# untitled.net
KiCad netlist of a schematic drawn in EAGLE
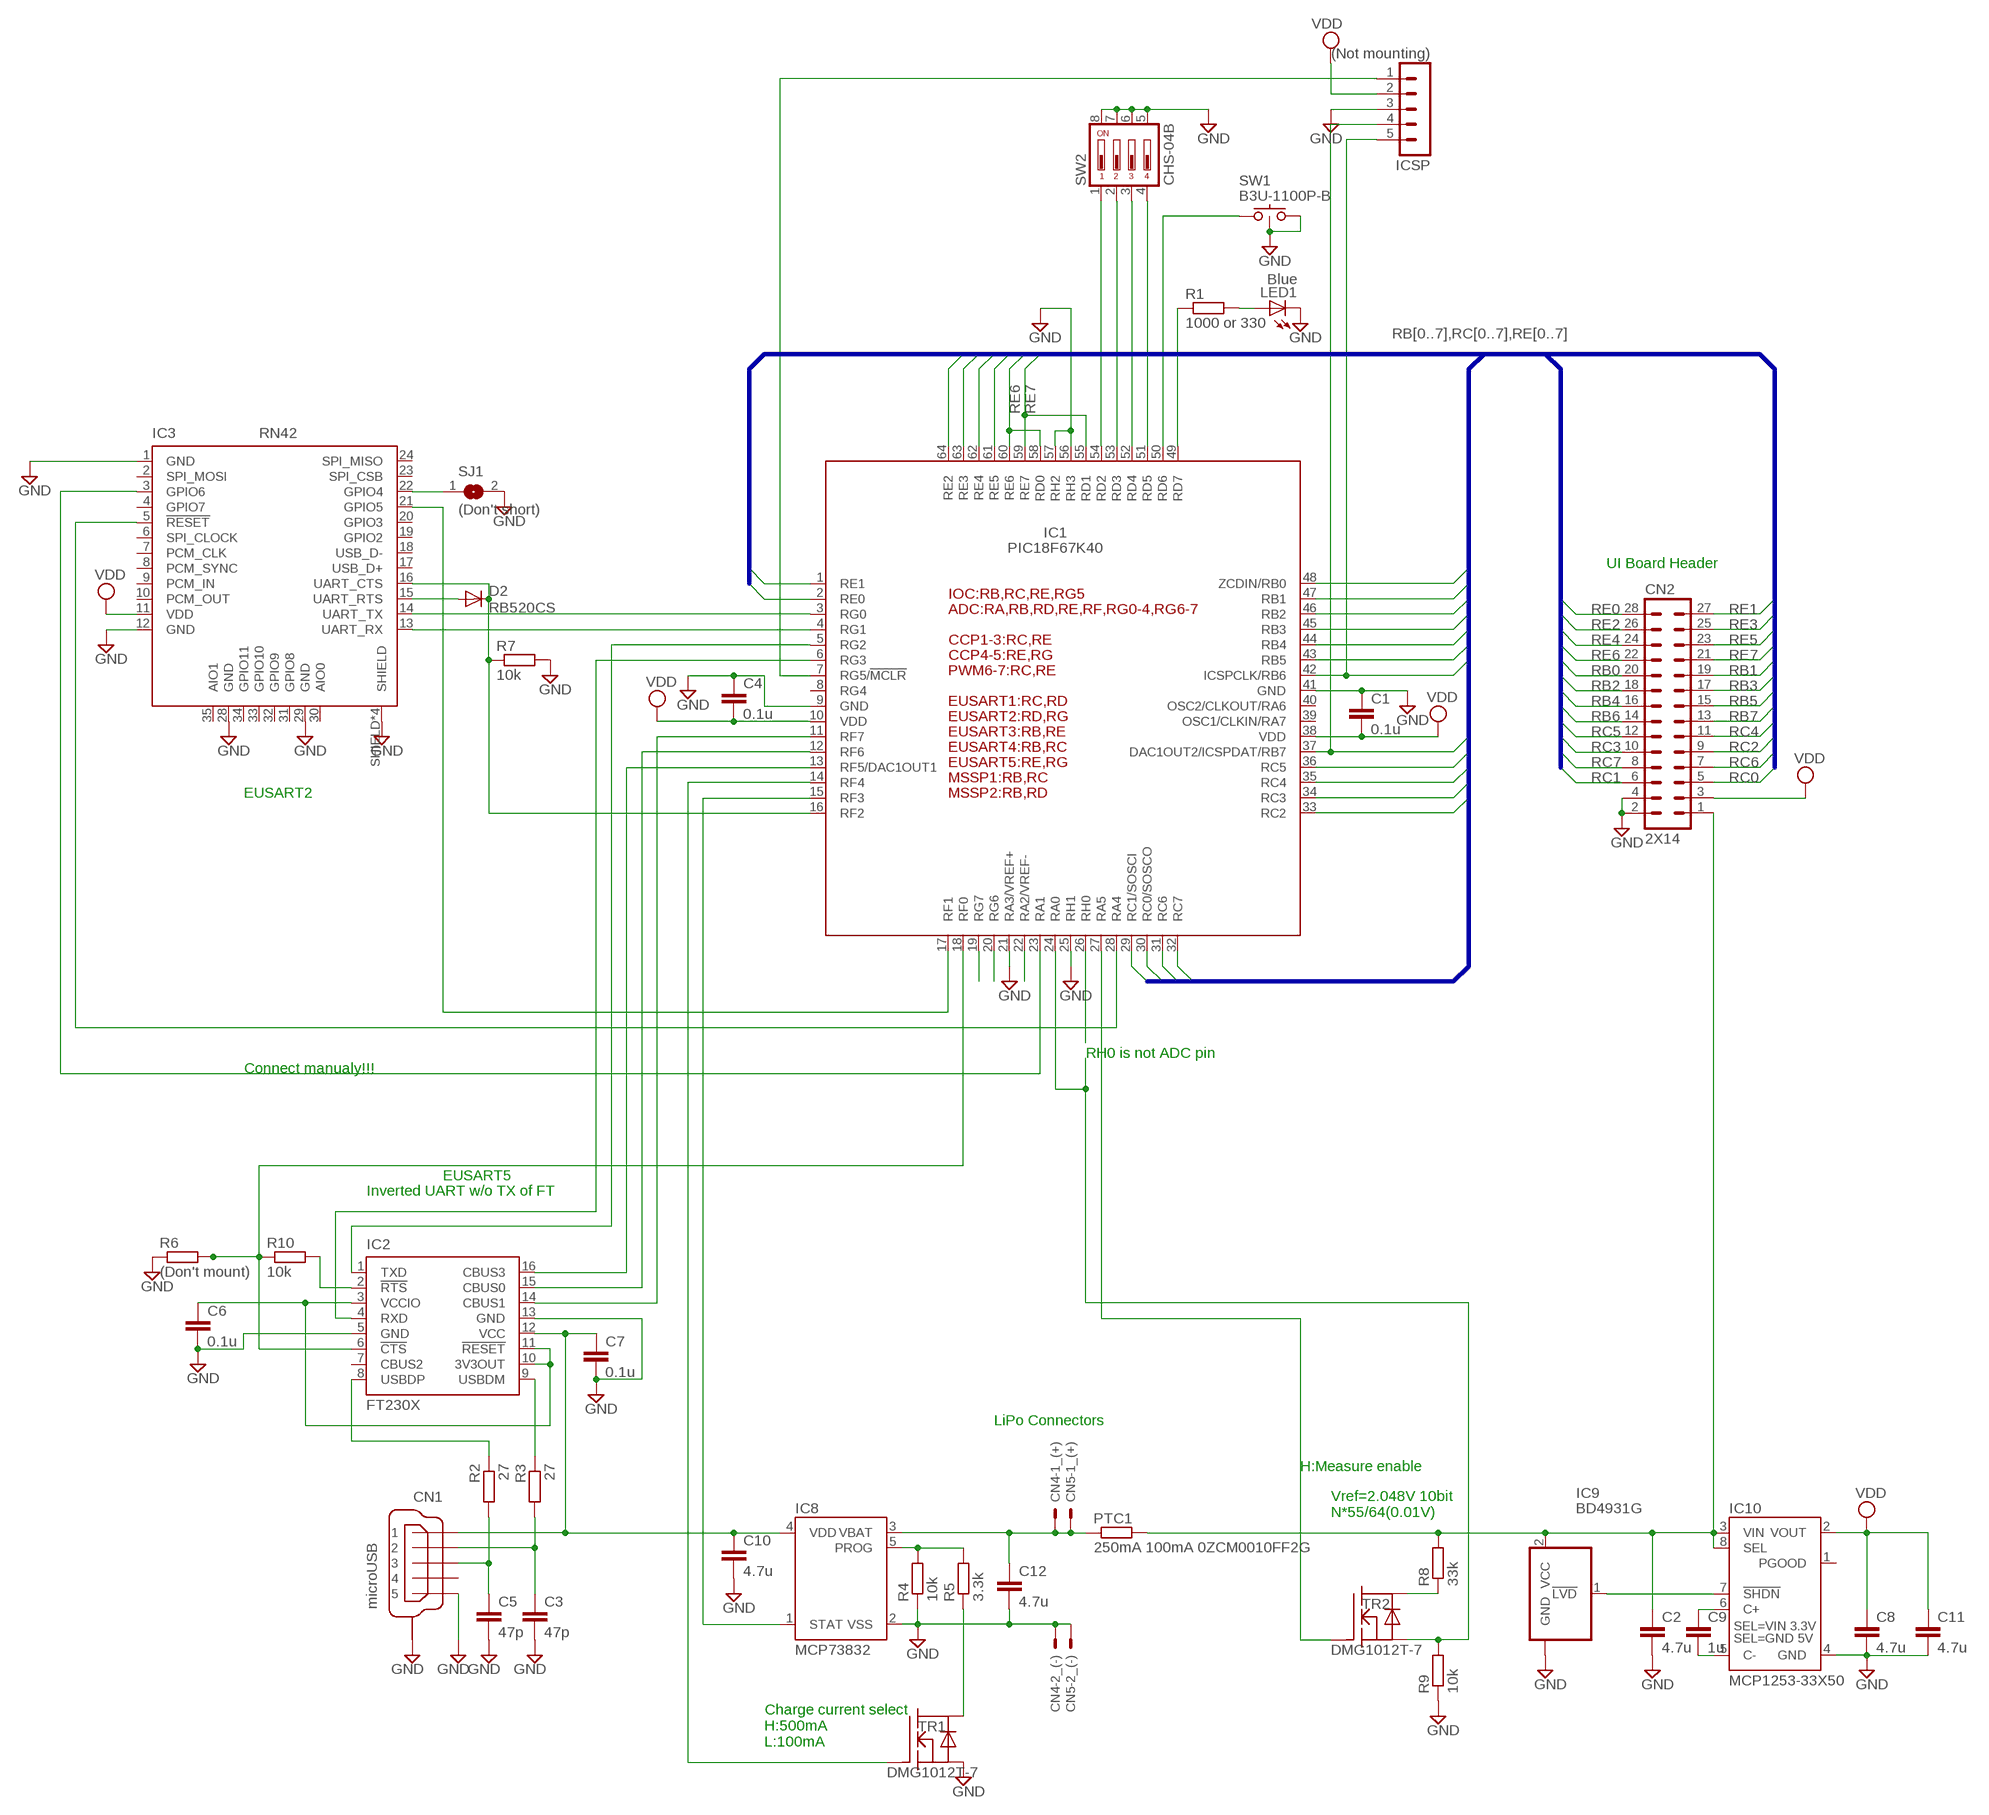
[diagram p0: schematic, sheet 1]

(export (version "E")
  (design (tool "Eeschema 10.0.6"))
  (components
    (comp (ref "C1")
      (value "0.1u")
      (footprint "eagle-import:C0402-SS")
      (libsource (lib "eagle-import") (part "C-EUC0402-SS"))
    )
    (comp (ref "C2")
      (value "4.7u")
      (footprint "eagle-import:C0805")
      (libsource (lib "eagle-import") (part "C-EUC0805"))
    )
    (comp (ref "C3")
      (value "47p")
      (footprint "eagle-import:C0402-SS")
      (libsource (lib "eagle-import") (part "C-EUC0402-SS"))
    )
    (comp (ref "C4")
      (value "0.1u")
      (footprint "eagle-import:C0402-SS")
      (libsource (lib "eagle-import") (part "C-EUC0402-SS"))
    )
    (comp (ref "C5")
      (value "47p")
      (footprint "eagle-import:C0402-SS")
      (libsource (lib "eagle-import") (part "C-EUC0402-SS"))
    )
    (comp (ref "C6")
      (value "0.1u")
      (footprint "eagle-import:C0402-SS")
      (libsource (lib "eagle-import") (part "C-EUC0402-SS"))
    )
    (comp (ref "C7")
      (value "0.1u")
      (footprint "eagle-import:C0402-SS")
      (libsource (lib "eagle-import") (part "C-EUC0402-SS"))
    )
    (comp (ref "C8")
      (value "4.7u")
      (footprint "eagle-import:C0805")
      (libsource (lib "eagle-import") (part "C-EUC0805"))
    )
    (comp (ref "C9")
      (value "1u")
      (footprint "eagle-import:C0805")
      (libsource (lib "eagle-import") (part "C-EUC0805"))
    )
    (comp (ref "C10")
      (value "4.7u")
      (footprint "eagle-import:C0805")
      (libsource (lib "eagle-import") (part "C-EUC0805"))
    )
    (comp (ref "C11")
      (value "4.7u")
      (footprint "eagle-import:C0805")
      (libsource (lib "eagle-import") (part "C-EUC0805"))
    )
    (comp (ref "C12")
      (value "4.7u")
      (footprint "eagle-import:C0805")
      (libsource (lib "eagle-import") (part "C-EUC0805"))
    )
    (comp (ref "CN1")
      (value "microUSB")
      (footprint "eagle-import:10118194-0001LF")
      (libsource (lib "eagle-import") (part "MICROUSB(10118194-0001LF)"))
    )
    (comp (ref "CN2")
      (value "2X14")
      (footprint "eagle-import:2MM_14X2")
      (libsource (lib "eagle-import") (part "2X14"))
    )
    (comp (ref "CN4")
      (value "2P_(POWER)PH_S")
      (footprint "eagle-import:PH-2_S")
      (libsource (lib "eagle-import") (part "2P_(POWER)PH_S"))
    )
    (comp (ref "CN5")
      (value "2P_(POWER)PH_S")
      (footprint "eagle-import:PH-2_S")
      (libsource (lib "eagle-import") (part "2P_(POWER)PH_S"))
    )
    (comp (ref "D2")
      (value "RB520CS")
      (footprint "eagle-import:VMN2")
      (libsource (lib "eagle-import") (part "DIODE-VMN2"))
    )
    (comp (ref "IC1")
      (value "PIC18F67K40")
      (footprint "eagle-import:TQFP64-10X10")
      (libsource (lib "eagle-import") (part "PIC18F67K40"))
    )
    (comp (ref "IC2")
      (value "FT230X")
      (footprint "eagle-import:SSOP16")
      (libsource (lib "eagle-import") (part "FT230XS"))
    )
    (comp (ref "IC3")
      (value "RN42")
      (footprint "eagle-import:RN-42")
      (libsource (lib "eagle-import") (part "RN-42"))
    )
    (comp (ref "IC8")
      (value "MCP73832")
      (footprint "eagle-import:SOT23-5L")
      (libsource (lib "eagle-import") (part "MCP73831"))
    )
    (comp (ref "IC9")
      (value "BD4931G")
      (footprint "eagle-import:SOT23-5L")
      (libsource (lib "eagle-import") (part "BD48XX"))
    )
    (comp (ref "IC10")
      (value "MCP1253-33X50")
      (footprint "eagle-import:MSOP8")
      (libsource (lib "eagle-import") (part "MCP1253-33X50"))
    )
    (comp (ref "ICSP")
      (value "(Not mounting)")
      (footprint "eagle-import:MA05-1")
      (libsource (lib "eagle-import") (part "MA05-1"))
    )
    (comp (ref "LED1")
      (value "Blue")
      (footprint "eagle-import:CHIP-LED1005")
      (libsource (lib "eagle-import") (part "LED1005"))
    )
    (comp (ref "PTC1")
      (value "250mA 100mA 0ZCM0010FF2G")
      (footprint "eagle-import:R0603")
      (libsource (lib "eagle-import") (part "R-EU_R0603"))
    )
    (comp (ref "R1")
      (value "1000 or 330")
      (footprint "eagle-import:R0402-SS")
      (libsource (lib "eagle-import") (part "R-EU_R0402-SS"))
    )
    (comp (ref "R2")
      (value "27")
      (footprint "eagle-import:R0402-SS")
      (libsource (lib "eagle-import") (part "R-EU_R0402-SS"))
    )
    (comp (ref "R3")
      (value "27")
      (footprint "eagle-import:R0402-SS")
      (libsource (lib "eagle-import") (part "R-EU_R0402-SS"))
    )
    (comp (ref "R4")
      (value "10k")
      (footprint "eagle-import:R0402-SS")
      (libsource (lib "eagle-import") (part "R-EU_R0402-SS"))
    )
    (comp (ref "R5")
      (value "3.3k")
      (footprint "eagle-import:R0402-SS")
      (libsource (lib "eagle-import") (part "R-EU_R0402-SS"))
    )
    (comp (ref "R6")
      (value "(Don't mount)")
      (footprint "eagle-import:R0402-SS")
      (libsource (lib "eagle-import") (part "R-EU_R0402-SS"))
    )
    (comp (ref "R7")
      (value "10k")
      (footprint "eagle-import:R0402-SS")
      (libsource (lib "eagle-import") (part "R-EU_R0402-SS"))
    )
    (comp (ref "R8")
      (value "33k")
      (footprint "eagle-import:R0402-SS")
      (libsource (lib "eagle-import") (part "R-EU_R0402-SS"))
    )
    (comp (ref "R9")
      (value "10k")
      (footprint "eagle-import:R0402-SS")
      (libsource (lib "eagle-import") (part "R-EU_R0402-SS"))
    )
    (comp (ref "R10")
      (value "10k")
      (footprint "eagle-import:R0402-SS")
      (libsource (lib "eagle-import") (part "R-EU_R0402-SS"))
    )
    (comp (ref "SJ1")
      (value "(Don't short)")
      (footprint "eagle-import:SJ")
      (libsource (lib "eagle-import") (part "SJ"))
    )
    (comp (ref "SW1")
      (value "B3U-1100P-B")
      (footprint "eagle-import:B3U-1100P-B")
      (libsource (lib "eagle-import") (part "SW_WITH_EARTH(B3U-1100P)"))
    )
    (comp (ref "SW2")
      (value "CHS-04B")
      (footprint "eagle-import:CHS-04B")
      (libsource (lib "eagle-import") (part "CHS-04B"))
    )
    (comp (ref "TR1")
      (value "DMG1012T-7")
      (footprint "eagle-import:SOT523")
      (libsource (lib "eagle-import") (part "NMOSSOT523"))
    )
    (comp (ref "TR2")
      (value "DMG1012T-7")
      (footprint "eagle-import:SOT523")
      (libsource (lib "eagle-import") (part "NMOSSOT523"))
    )
  )
  (nets
    (net (code "1") (name "/RB0") (class "Default")
      (node (ref "CN2") (pin "20") (pinfunction "20_20") (pintype "passive"))
      (node (ref "IC1") (pin "48") (pinfunction "ZCDIN/RB0_48") (pintype "bidirectional"))
    )
    (net (code "2") (name "/RB1") (class "Default")
      (node (ref "CN2") (pin "19") (pinfunction "19_19") (pintype "passive"))
      (node (ref "IC1") (pin "47") (pinfunction "RB1_47") (pintype "bidirectional"))
    )
    (net (code "3") (name "/RB2") (class "Default")
      (node (ref "CN2") (pin "18") (pinfunction "18_18") (pintype "passive"))
      (node (ref "IC1") (pin "46") (pinfunction "RB2_46") (pintype "bidirectional"))
    )
    (net (code "4") (name "/RB3") (class "Default")
      (node (ref "CN2") (pin "17") (pinfunction "17_17") (pintype "passive"))
      (node (ref "IC1") (pin "45") (pinfunction "RB3_45") (pintype "bidirectional"))
    )
    (net (code "5") (name "/RB4") (class "Default")
      (node (ref "CN2") (pin "16") (pinfunction "16_16") (pintype "passive"))
      (node (ref "IC1") (pin "44") (pinfunction "RB4_44") (pintype "bidirectional"))
    )
    (net (code "6") (name "/RB5") (class "Default")
      (node (ref "CN2") (pin "15") (pinfunction "15_15") (pintype "passive"))
      (node (ref "IC1") (pin "43") (pinfunction "RB5_43") (pintype "bidirectional"))
    )
    (net (code "7") (name "/RB6") (class "Default")
      (node (ref "CN2") (pin "14") (pinfunction "14_14") (pintype "passive"))
      (node (ref "IC1") (pin "42") (pinfunction "ICSPCLK/RB6_42") (pintype "bidirectional"))
      (node (ref "ICSP") (pin "5") (pinfunction "5_5") (pintype "passive"))
    )
    (net (code "8") (name "/RB7") (class "Default")
      (node (ref "CN2") (pin "13") (pinfunction "13_13") (pintype "passive"))
      (node (ref "IC1") (pin "37") (pinfunction "DAC1OUT2/ICSPDAT/RB7_37") (pintype "bidirectional"))
      (node (ref "ICSP") (pin "4") (pinfunction "4_4") (pintype "passive"))
    )
    (net (code "9") (name "/RC0") (class "Default")
      (node (ref "CN2") (pin "5") (pinfunction "5_5") (pintype "passive"))
      (node (ref "IC1") (pin "30") (pinfunction "RC0/SOSCO_30") (pintype "bidirectional"))
    )
    (net (code "10") (name "/RC1") (class "Default")
      (node (ref "CN2") (pin "6") (pinfunction "6_6") (pintype "passive"))
      (node (ref "IC1") (pin "29") (pinfunction "RC1/SOSCI_29") (pintype "bidirectional"))
    )
    (net (code "11") (name "/RC2") (class "Default")
      (node (ref "CN2") (pin "9") (pinfunction "9_9") (pintype "passive"))
      (node (ref "IC1") (pin "33") (pinfunction "RC2_33") (pintype "bidirectional"))
    )
    (net (code "12") (name "/RC3") (class "Default")
      (node (ref "CN2") (pin "10") (pinfunction "10_10") (pintype "passive"))
      (node (ref "IC1") (pin "34") (pinfunction "RC3_34") (pintype "bidirectional"))
    )
    (net (code "13") (name "/RC4") (class "Default")
      (node (ref "CN2") (pin "11") (pinfunction "11_11") (pintype "passive"))
      (node (ref "IC1") (pin "35") (pinfunction "RC4_35") (pintype "bidirectional"))
    )
    (net (code "14") (name "/RC5") (class "Default")
      (node (ref "CN2") (pin "12") (pinfunction "12_12") (pintype "passive"))
      (node (ref "IC1") (pin "36") (pinfunction "RC5_36") (pintype "bidirectional"))
    )
    (net (code "15") (name "/RC6") (class "Default")
      (node (ref "CN2") (pin "7") (pinfunction "7_7") (pintype "passive"))
      (node (ref "IC1") (pin "31") (pinfunction "RC6_31") (pintype "bidirectional"))
    )
    (net (code "16") (name "/RC7") (class "Default")
      (node (ref "CN2") (pin "8") (pinfunction "8_8") (pintype "passive"))
      (node (ref "IC1") (pin "32") (pinfunction "RC7_32") (pintype "bidirectional"))
    )
    (net (code "17") (name "/RE0") (class "Default")
      (node (ref "CN2") (pin "28") (pinfunction "28_28") (pintype "passive"))
      (node (ref "IC1") (pin "2") (pinfunction "RE0_2") (pintype "bidirectional"))
    )
    (net (code "18") (name "/RE1") (class "Default")
      (node (ref "CN2") (pin "27") (pinfunction "27_27") (pintype "passive"))
      (node (ref "IC1") (pin "1") (pinfunction "RE1_1") (pintype "bidirectional"))
    )
    (net (code "19") (name "/RE2") (class "Default")
      (node (ref "CN2") (pin "26") (pinfunction "26_26") (pintype "passive"))
      (node (ref "IC1") (pin "64") (pinfunction "RE2_64") (pintype "bidirectional"))
    )
    (net (code "20") (name "/RE3") (class "Default")
      (node (ref "CN2") (pin "25") (pinfunction "25_25") (pintype "passive"))
      (node (ref "IC1") (pin "63") (pinfunction "RE3_63") (pintype "bidirectional"))
    )
    (net (code "21") (name "/RE4") (class "Default")
      (node (ref "CN2") (pin "24") (pinfunction "24_24") (pintype "passive"))
      (node (ref "IC1") (pin "62") (pinfunction "RE4_62") (pintype "bidirectional"))
    )
    (net (code "22") (name "/RE5") (class "Default")
      (node (ref "CN2") (pin "23") (pinfunction "23_23") (pintype "passive"))
      (node (ref "IC1") (pin "61") (pinfunction "RE5_61") (pintype "bidirectional"))
    )
    (net (code "23") (name "/RE6") (class "Default")
      (node (ref "CN2") (pin "22") (pinfunction "22_22") (pintype "passive"))
      (node (ref "IC1") (pin "58") (pinfunction "RD0_58") (pintype "bidirectional"))
      (node (ref "IC1") (pin "60") (pinfunction "RE6_60") (pintype "bidirectional"))
    )
    (net (code "24") (name "/RE7") (class "Default")
      (node (ref "CN2") (pin "21") (pinfunction "21_21") (pintype "passive"))
      (node (ref "IC1") (pin "55") (pinfunction "RD1_55") (pintype "bidirectional"))
      (node (ref "IC1") (pin "59") (pinfunction "RE7_59") (pintype "bidirectional"))
    )
    (net (code "26") (name "GND") (class "Default")
      (node (ref "C1") (pin "1") (pinfunction "1_1") (pintype "passive"))
      (node (ref "C10") (pin "2") (pinfunction "2_2") (pintype "passive"))
      (node (ref "C11") (pin "2") (pinfunction "2_2") (pintype "passive"))
      (node (ref "C12") (pin "2") (pinfunction "2_2") (pintype "passive"))
      (node (ref "C2") (pin "2") (pinfunction "2_2") (pintype "passive"))
      (node (ref "C3") (pin "2") (pinfunction "2_2") (pintype "passive"))
      (node (ref "C4") (pin "1") (pinfunction "1_1") (pintype "passive"))
      (node (ref "C5") (pin "2") (pinfunction "2_2") (pintype "passive"))
      (node (ref "C6") (pin "2") (pinfunction "2_2") (pintype "passive"))
      (node (ref "C7") (pin "2") (pinfunction "2_2") (pintype "passive"))
      (node (ref "C8") (pin "2") (pinfunction "2_2") (pintype "passive"))
      (node (ref "CN1") (pin "P$5") (pinfunction "5_P$5") (pintype "passive"))
      (node (ref "CN1") (pin "P$6") (pinfunction "S_P$6") (pintype "passive"))
      (node (ref "CN1") (pin "P$7") (pinfunction "S_P$7") (pintype "passive"))
      (node (ref "CN1") (pin "S1") (pinfunction "S_S1") (pintype "passive"))
      (node (ref "CN1") (pin "S10") (pinfunction "S_S10") (pintype "passive"))
      (node (ref "CN1") (pin "S2") (pinfunction "S_S2") (pintype "passive"))
      (node (ref "CN1") (pin "S3") (pinfunction "S_S3") (pintype "passive"))
      (node (ref "CN1") (pin "S4") (pinfunction "S_S4") (pintype "passive"))
      (node (ref "CN1") (pin "S5") (pinfunction "S_S5") (pintype "passive"))
      (node (ref "CN1") (pin "S6") (pinfunction "S_S6") (pintype "passive"))
      (node (ref "CN1") (pin "S7") (pinfunction "S_S7") (pintype "passive"))
      (node (ref "CN1") (pin "S8") (pinfunction "S_S8") (pintype "passive"))
      (node (ref "CN1") (pin "S9") (pinfunction "S_S9") (pintype "passive"))
      (node (ref "CN2") (pin "2") (pinfunction "2_2") (pintype "passive"))
      (node (ref "CN2") (pin "4") (pinfunction "4_4") (pintype "passive"))
      (node (ref "CN4") (pin "2") (pinfunction "S_2") (pintype "passive"))
      (node (ref "CN5") (pin "2") (pinfunction "S_2") (pintype "passive"))
      (node (ref "IC1") (pin "21") (pinfunction "RA3/VREF+_21") (pintype "bidirectional"))
      (node (ref "IC1") (pin "25") (pinfunction "RH1_25") (pintype "bidirectional"))
      (node (ref "IC1") (pin "41") (pinfunction "GND_41") (pintype "power_in"))
      (node (ref "IC1") (pin "56") (pinfunction "RH3_56") (pintype "bidirectional"))
      (node (ref "IC1") (pin "57") (pinfunction "RH2_57") (pintype "bidirectional"))
      (node (ref "IC1") (pin "9") (pinfunction "GND_9") (pintype "power_in"))
      (node (ref "IC10") (pin "4") (pinfunction "GND_4") (pintype "power_in"))
      (node (ref "IC2") (pin "13") (pinfunction "GND_13") (pintype "power_in"))
      (node (ref "IC2") (pin "5") (pinfunction "GND_5") (pintype "power_in"))
      (node (ref "IC3") (pin "1") (pinfunction "GND_1") (pintype "bidirectional"))
      (node (ref "IC3") (pin "12") (pinfunction "GND_12") (pintype "bidirectional"))
      (node (ref "IC3") (pin "28") (pinfunction "GND_28") (pintype "bidirectional"))
      (node (ref "IC3") (pin "29") (pinfunction "GND_29") (pintype "bidirectional"))
      (node (ref "IC3") (pin "SHIELD") (pinfunction "SHIELD_SHIELD") (pintype "bidirectional"))
      (node (ref "IC3") (pin "SHIELD@1") (pinfunction "SHIELD_SHIELD@1") (pintype "bidirectional"))
      (node (ref "IC3") (pin "SHIELD@2") (pinfunction "SHIELD_SHIELD@2") (pintype "bidirectional"))
      (node (ref "IC3") (pin "SHIELD@3") (pinfunction "SHIELD_SHIELD@3") (pintype "bidirectional"))
      (node (ref "IC8") (pin "2") (pinfunction "VSS_2") (pintype "power_in"))
      (node (ref "IC9") (pin "3") (pinfunction "GND_3") (pintype "power_in"))
      (node (ref "ICSP") (pin "3") (pinfunction "3_3") (pintype "passive"))
      (node (ref "LED1") (pin "C") (pinfunction "C_C") (pintype "passive"))
      (node (ref "R4") (pin "1") (pinfunction "1_1") (pintype "passive"))
      (node (ref "R6") (pin "1") (pinfunction "1_1") (pintype "passive"))
      (node (ref "R7") (pin "2") (pinfunction "2_2") (pintype "passive"))
      (node (ref "R9") (pin "1") (pinfunction "1_1") (pintype "passive"))
      (node (ref "SJ1") (pin "2") (pinfunction "2_2") (pintype "passive"))
      (node (ref "SW1") (pin "P$2") (pinfunction "P$2_P$2") (pintype "passive"))
      (node (ref "SW1") (pin "P$3") (pinfunction "P$3_P$3") (pintype "passive"))
      (node (ref "SW2") (pin "5") (pinfunction "5_5") (pintype "passive"))
      (node (ref "SW2") (pin "6") (pinfunction "6_6") (pintype "passive"))
      (node (ref "SW2") (pin "7") (pinfunction "7_7") (pintype "passive"))
      (node (ref "SW2") (pin "8") (pinfunction "8_8") (pintype "passive"))
      (node (ref "TR1") (pin "2") (pinfunction "S_2") (pintype "bidirectional"))
    )
    (net (code "27") (name "Net-(CN1-1)") (class "Default")
      (node (ref "C10") (pin "1") (pinfunction "1_1") (pintype "passive"))
      (node (ref "C7") (pin "1") (pinfunction "1_1") (pintype "passive"))
      (node (ref "CN1") (pin "P$1") (pinfunction "1_P$1") (pintype "passive"))
      (node (ref "IC2") (pin "12") (pinfunction "VCC_12") (pintype "power_in"))
      (node (ref "IC8") (pin "4") (pinfunction "VDD_4") (pintype "power_in"))
    )
    (net (code "28") (name "Net-(CN1-2)") (class "Default")
      (node (ref "C3") (pin "1") (pinfunction "1_1") (pintype "passive"))
      (node (ref "CN1") (pin "P$2") (pinfunction "2_P$2") (pintype "passive"))
      (node (ref "R3") (pin "2") (pinfunction "2_2") (pintype "passive"))
    )
    (net (code "29") (name "Net-(CN1-3)") (class "Default")
      (node (ref "C5") (pin "1") (pinfunction "1_1") (pintype "passive"))
      (node (ref "CN1") (pin "P$3") (pinfunction "3_P$3") (pintype "passive"))
      (node (ref "R2") (pin "2") (pinfunction "2_2") (pintype "passive"))
    )
    (net (code "30") (name "Net-(CN4A-S)") (class "Default")
      (node (ref "C12") (pin "1") (pinfunction "1_1") (pintype "passive"))
      (node (ref "CN4") (pin "1") (pinfunction "S_1") (pintype "passive"))
      (node (ref "CN5") (pin "1") (pinfunction "S_1") (pintype "passive"))
      (node (ref "IC8") (pin "3") (pinfunction "VBAT_3") (pintype "output"))
      (node (ref "PTC1") (pin "1") (pinfunction "1_1") (pintype "passive"))
    )
    (net (code "31") (name "Net-(IC1-RA0)") (class "Default")
      (node (ref "IC1") (pin "24") (pinfunction "RA0_24") (pintype "bidirectional"))
      (node (ref "R9") (pin "2") (pinfunction "2_2") (pintype "passive"))
      (node (ref "TR2") (pin "2") (pinfunction "S_2") (pintype "bidirectional"))
    )
    (net (code "32") (name "Net-(IC1-RA1)") (class "Default")
      (node (ref "IC1") (pin "23") (pinfunction "RA1_23") (pintype "bidirectional"))
      (node (ref "IC3") (pin "3") (pinfunction "GPIO6_3") (pintype "bidirectional"))
    )
    (net (code "33") (name "Net-(IC1-RA4)") (class "Default")
      (node (ref "IC1") (pin "28") (pinfunction "RA4_28") (pintype "bidirectional"))
      (node (ref "IC3") (pin "5") (pinfunction "~{RESET}_5") (pintype "bidirectional"))
    )
    (net (code "34") (name "Net-(IC1-RA5)") (class "Default")
      (node (ref "IC1") (pin "27") (pinfunction "RA5_27") (pintype "bidirectional"))
      (node (ref "TR2") (pin "1") (pinfunction "G_1") (pintype "bidirectional"))
    )
    (net (code "35") (name "Net-(IC1-RD2)") (class "Default")
      (node (ref "IC1") (pin "54") (pinfunction "RD2_54") (pintype "bidirectional"))
      (node (ref "SW2") (pin "1") (pinfunction "1_1") (pintype "passive"))
    )
    (net (code "36") (name "Net-(IC1-RD3)") (class "Default")
      (node (ref "IC1") (pin "53") (pinfunction "RD3_53") (pintype "bidirectional"))
      (node (ref "SW2") (pin "2") (pinfunction "2_2") (pintype "passive"))
    )
    (net (code "37") (name "Net-(IC1-RD4)") (class "Default")
      (node (ref "IC1") (pin "52") (pinfunction "RD4_52") (pintype "bidirectional"))
      (node (ref "SW2") (pin "3") (pinfunction "3_3") (pintype "passive"))
    )
    (net (code "38") (name "Net-(IC1-RD5)") (class "Default")
      (node (ref "IC1") (pin "51") (pinfunction "RD5_51") (pintype "bidirectional"))
      (node (ref "SW2") (pin "4") (pinfunction "4_4") (pintype "passive"))
    )
    (net (code "39") (name "Net-(IC1-RD6)") (class "Default")
      (node (ref "IC1") (pin "50") (pinfunction "RD6_50") (pintype "bidirectional"))
      (node (ref "SW1") (pin "P$1") (pinfunction "P$1_P$1") (pintype "passive"))
    )
    (net (code "40") (name "Net-(IC1-RD7)") (class "Default")
      (node (ref "IC1") (pin "49") (pinfunction "RD7_49") (pintype "bidirectional"))
      (node (ref "R1") (pin "1") (pinfunction "1_1") (pintype "passive"))
    )
    (net (code "41") (name "Net-(IC1-RF0)") (class "Default")
      (node (ref "IC1") (pin "18") (pinfunction "RF0_18") (pintype "bidirectional"))
      (node (ref "IC2") (pin "6") (pinfunction "~{CTS}_6") (pintype "input"))
      (node (ref "R10") (pin "1") (pinfunction "1_1") (pintype "passive"))
      (node (ref "R6") (pin "2") (pinfunction "2_2") (pintype "passive"))
    )
    (net (code "42") (name "Net-(IC1-RF1)") (class "Default")
      (node (ref "IC1") (pin "17") (pinfunction "RF1_17") (pintype "bidirectional"))
      (node (ref "IC3") (pin "21") (pinfunction "GPIO5_21") (pintype "bidirectional"))
    )
    (net (code "43") (name "Net-(IC1-RF2)") (class "Default")
      (node (ref "D2") (pin "C") (pinfunction "C_C") (pintype "passive"))
      (node (ref "IC1") (pin "16") (pinfunction "RF2_16") (pintype "bidirectional"))
      (node (ref "IC3") (pin "16") (pinfunction "UART_CTS_16") (pintype "bidirectional"))
      (node (ref "R7") (pin "1") (pinfunction "1_1") (pintype "passive"))
    )
    (net (code "44") (name "Net-(IC1-RF3)") (class "Default")
      (node (ref "IC1") (pin "15") (pinfunction "RF3_15") (pintype "bidirectional"))
      (node (ref "IC8") (pin "1") (pinfunction "STAT_1") (pintype "output"))
    )
    (net (code "45") (name "Net-(IC1-RF4)") (class "Default")
      (node (ref "IC1") (pin "14") (pinfunction "RF4_14") (pintype "bidirectional"))
      (node (ref "TR1") (pin "1") (pinfunction "G_1") (pintype "bidirectional"))
    )
    (net (code "46") (name "Net-(IC1-RF5{slash}DAC1OUT1)") (class "Default")
      (node (ref "IC1") (pin "13") (pinfunction "RF5/DAC1OUT1_13") (pintype "bidirectional"))
      (node (ref "IC2") (pin "16") (pinfunction "CBUS3_16") (pintype "bidirectional"))
    )
    (net (code "47") (name "Net-(IC1-RF6)") (class "Default")
      (node (ref "IC1") (pin "12") (pinfunction "RF6_12") (pintype "bidirectional"))
      (node (ref "IC2") (pin "15") (pinfunction "CBUS0_15") (pintype "bidirectional"))
    )
    (net (code "48") (name "Net-(IC1-RF7)") (class "Default")
      (node (ref "IC1") (pin "11") (pinfunction "RF7_11") (pintype "bidirectional"))
      (node (ref "IC2") (pin "14") (pinfunction "CBUS1_14") (pintype "bidirectional"))
    )
    (net (code "49") (name "Net-(IC1-RG0)") (class "Default")
      (node (ref "IC1") (pin "3") (pinfunction "RG0_3") (pintype "bidirectional"))
      (node (ref "IC3") (pin "14") (pinfunction "UART_TX_14") (pintype "bidirectional"))
    )
    (net (code "50") (name "Net-(IC1-RG1)") (class "Default")
      (node (ref "IC1") (pin "4") (pinfunction "RG1_4") (pintype "bidirectional"))
      (node (ref "IC3") (pin "13") (pinfunction "UART_RX_13") (pintype "bidirectional"))
    )
    (net (code "51") (name "Net-(IC1-RG2)") (class "Default")
      (node (ref "IC1") (pin "5") (pinfunction "RG2_5") (pintype "bidirectional"))
      (node (ref "IC2") (pin "1") (pinfunction "TXD_1") (pintype "output"))
    )
    (net (code "52") (name "Net-(IC1-RG3)") (class "Default")
      (node (ref "IC1") (pin "6") (pinfunction "RG3_6") (pintype "bidirectional"))
      (node (ref "IC2") (pin "4") (pinfunction "RXD_4") (pintype "input"))
    )
    (net (code "53") (name "Net-(IC1-RG5{slash}~{MCLR})") (class "Default")
      (node (ref "IC1") (pin "7") (pinfunction "RG5/~{MCLR}_7") (pintype "input"))
      (node (ref "ICSP") (pin "1") (pinfunction "1_1") (pintype "passive"))
    )
    (net (code "54") (name "Net-(IC2-3V3OUT)") (class "Default")
      (node (ref "C6") (pin "1") (pinfunction "1_1") (pintype "passive"))
      (node (ref "IC2") (pin "10") (pinfunction "3V3OUT_10") (pintype "output"))
      (node (ref "IC2") (pin "11") (pinfunction "~{RESET}_11") (pintype "input"))
      (node (ref "IC2") (pin "3") (pinfunction "VCCIO_3") (pintype "power_in"))
    )
    (net (code "55") (name "Net-(IC2-USBDM)") (class "Default")
      (node (ref "IC2") (pin "9") (pinfunction "USBDM_9") (pintype "input"))
      (node (ref "R3") (pin "1") (pinfunction "1_1") (pintype "passive"))
    )
    (net (code "56") (name "Net-(IC2-USBDP)") (class "Default")
      (node (ref "IC2") (pin "8") (pinfunction "USBDP_8") (pintype "input"))
      (node (ref "R2") (pin "1") (pinfunction "1_1") (pintype "passive"))
    )
    (net (code "57") (name "Net-(IC2-~{RTS})") (class "Default")
      (node (ref "IC2") (pin "2") (pinfunction "~{RTS}_2") (pintype "output"))
      (node (ref "R10") (pin "2") (pinfunction "2_2") (pintype "passive"))
    )
    (net (code "58") (name "Net-(IC3-GPIO4)") (class "Default")
      (node (ref "IC3") (pin "22") (pinfunction "GPIO4_22") (pintype "bidirectional"))
      (node (ref "SJ1") (pin "1") (pinfunction "1_1") (pintype "passive"))
    )
    (net (code "59") (name "Net-(IC3-UART_RTS)") (class "Default")
      (node (ref "D2") (pin "A") (pinfunction "A_A") (pintype "passive"))
      (node (ref "IC3") (pin "15") (pinfunction "UART_RTS_15") (pintype "bidirectional"))
    )
    (net (code "60") (name "Net-(IC8-PROG)") (class "Default")
      (node (ref "IC8") (pin "5") (pinfunction "PROG_5") (pintype "input"))
      (node (ref "R4") (pin "2") (pinfunction "2_2") (pintype "passive"))
      (node (ref "R5") (pin "2") (pinfunction "2_2") (pintype "passive"))
    )
    (net (code "61") (name "Net-(IC10-C+)") (class "Default")
      (node (ref "C9") (pin "1") (pinfunction "1_1") (pintype "passive"))
      (node (ref "IC10") (pin "6") (pinfunction "C+_6") (pintype "passive"))
    )
    (net (code "62") (name "Net-(IC10-C-)") (class "Default")
      (node (ref "C9") (pin "2") (pinfunction "2_2") (pintype "passive"))
      (node (ref "IC10") (pin "5") (pinfunction "C-_5") (pintype "passive"))
    )
    (net (code "63") (name "Net-(IC10-SEL)") (class "Default")
      (node (ref "C2") (pin "1") (pinfunction "1_1") (pintype "passive"))
      (node (ref "CN2") (pin "1") (pinfunction "1_1") (pintype "passive"))
      (node (ref "IC10") (pin "3") (pinfunction "VIN_3") (pintype "power_in"))
      (node (ref "IC10") (pin "8") (pinfunction "SEL_8") (pintype "input"))
      (node (ref "IC9") (pin "2") (pinfunction "VCC_2") (pintype "power_in"))
      (node (ref "PTC1") (pin "2") (pinfunction "2_2") (pintype "passive"))
      (node (ref "R8") (pin "2") (pinfunction "2_2") (pintype "passive"))
    )
    (net (code "64") (name "Net-(IC10-~{SHDN})") (class "Default")
      (node (ref "IC10") (pin "7") (pinfunction "~{SHDN}_7") (pintype "input"))
      (node (ref "IC9") (pin "1") (pinfunction "~{LVD}_1") (pintype "output"))
    )
    (net (code "65") (name "Net-(LED1-PadA)") (class "Default")
      (node (ref "LED1") (pin "A") (pinfunction "A_A") (pintype "passive"))
      (node (ref "R1") (pin "2") (pinfunction "2_2") (pintype "passive"))
    )
    (net (code "66") (name "Net-(TR1-D)") (class "Default")
      (node (ref "R5") (pin "1") (pinfunction "1_1") (pintype "passive"))
      (node (ref "TR1") (pin "3") (pinfunction "D_3") (pintype "bidirectional"))
    )
    (net (code "67") (name "Net-(TR2-D)") (class "Default")
      (node (ref "R8") (pin "1") (pinfunction "1_1") (pintype "passive"))
      (node (ref "TR2") (pin "3") (pinfunction "D_3") (pintype "bidirectional"))
    )
    (net (code "68") (name "VDD") (class "Default")
      (node (ref "C1") (pin "2") (pinfunction "2_2") (pintype "passive"))
      (node (ref "C11") (pin "1") (pinfunction "1_1") (pintype "passive"))
      (node (ref "C4") (pin "2") (pinfunction "2_2") (pintype "passive"))
      (node (ref "C8") (pin "1") (pinfunction "1_1") (pintype "passive"))
      (node (ref "CN2") (pin "3") (pinfunction "3_3") (pintype "passive"))
      (node (ref "IC1") (pin "10") (pinfunction "VDD_10") (pintype "power_in"))
      (node (ref "IC1") (pin "38") (pinfunction "VDD_38") (pintype "power_in"))
      (node (ref "IC10") (pin "2") (pinfunction "VOUT_2") (pintype "output"))
      (node (ref "IC3") (pin "11") (pinfunction "VDD_11") (pintype "bidirectional"))
      (node (ref "ICSP") (pin "2") (pinfunction "2_2") (pintype "passive"))
    )
    (net (code "69") (name "unconnected-(CN1-4-PadP$4)") (class "Default")
      (node (ref "CN1") (pin "P$4") (pinfunction "4_P$4") (pintype "passive"))
    )
    (net (code "70") (name "unconnected-(IC1-OSC1{slash}CLKIN{slash}RA7-Pad39)") (class "Default")
      (node (ref "IC1") (pin "39") (pinfunction "OSC1/CLKIN/RA7_39") (pintype "bidirectional"))
    )
    (net (code "71") (name "unconnected-(IC1-OSC2{slash}CLKOUT{slash}RA6-Pad40)") (class "Default")
      (node (ref "IC1") (pin "40") (pinfunction "OSC2/CLKOUT/RA6_40") (pintype "bidirectional"))
    )
    (net (code "72") (name "unconnected-(IC1-RA2{slash}VREF--Pad22)") (class "Default")
      (node (ref "IC1") (pin "22") (pinfunction "RA2/VREF-_22") (pintype "bidirectional"))
    )
    (net (code "73") (name "unconnected-(IC1-RG4-Pad8)") (class "Default")
      (node (ref "IC1") (pin "8") (pinfunction "RG4_8") (pintype "bidirectional"))
    )
    (net (code "74") (name "unconnected-(IC1-RG6-Pad20)") (class "Default")
      (node (ref "IC1") (pin "20") (pinfunction "RG6_20") (pintype "bidirectional"))
    )
    (net (code "75") (name "unconnected-(IC1-RG7-Pad19)") (class "Default")
      (node (ref "IC1") (pin "19") (pinfunction "RG7_19") (pintype "bidirectional"))
    )
    (net (code "76") (name "unconnected-(IC1-RH0-Pad26)") (class "Default")
      (node (ref "IC1") (pin "26") (pinfunction "RH0_26") (pintype "bidirectional"))
    )
    (net (code "77") (name "unconnected-(IC2-CBUS2-Pad7)") (class "Default")
      (node (ref "IC2") (pin "7") (pinfunction "CBUS2_7") (pintype "bidirectional"))
    )
    (net (code "78") (name "unconnected-(IC3-AIO0-Pad30)") (class "Default")
      (node (ref "IC3") (pin "30") (pinfunction "AIO0_30") (pintype "bidirectional"))
    )
    (net (code "79") (name "unconnected-(IC3-AIO1-Pad35)") (class "Default")
      (node (ref "IC3") (pin "35") (pinfunction "AIO1_35") (pintype "bidirectional"))
    )
    (net (code "80") (name "unconnected-(IC3-GPIO2-Pad19)") (class "Default")
      (node (ref "IC3") (pin "19") (pinfunction "GPIO2_19") (pintype "bidirectional"))
    )
    (net (code "81") (name "unconnected-(IC3-GPIO3-Pad20)") (class "Default")
      (node (ref "IC3") (pin "20") (pinfunction "GPIO3_20") (pintype "bidirectional"))
    )
    (net (code "82") (name "unconnected-(IC3-GPIO7-Pad4)") (class "Default")
      (node (ref "IC3") (pin "4") (pinfunction "GPIO7_4") (pintype "bidirectional"))
    )
    (net (code "83") (name "unconnected-(IC3-GPIO8-Pad31)") (class "Default")
      (node (ref "IC3") (pin "31") (pinfunction "GPIO8_31") (pintype "bidirectional"))
    )
    (net (code "84") (name "unconnected-(IC3-GPIO9-Pad32)") (class "Default")
      (node (ref "IC3") (pin "32") (pinfunction "GPIO9_32") (pintype "bidirectional"))
    )
    (net (code "85") (name "unconnected-(IC3-GPIO10-Pad33)") (class "Default")
      (node (ref "IC3") (pin "33") (pinfunction "GPIO10_33") (pintype "bidirectional"))
    )
    (net (code "86") (name "unconnected-(IC3-GPIO11-Pad34)") (class "Default")
      (node (ref "IC3") (pin "34") (pinfunction "GPIO11_34") (pintype "bidirectional"))
    )
    (net (code "87") (name "unconnected-(IC3-PCM_CLK-Pad7)") (class "Default")
      (node (ref "IC3") (pin "7") (pinfunction "PCM_CLK_7") (pintype "bidirectional"))
    )
    (net (code "88") (name "unconnected-(IC3-PCM_IN-Pad9)") (class "Default")
      (node (ref "IC3") (pin "9") (pinfunction "PCM_IN_9") (pintype "bidirectional"))
    )
    (net (code "89") (name "unconnected-(IC3-PCM_OUT-Pad10)") (class "Default")
      (node (ref "IC3") (pin "10") (pinfunction "PCM_OUT_10") (pintype "bidirectional"))
    )
    (net (code "90") (name "unconnected-(IC3-PCM_SYNC-Pad8)") (class "Default")
      (node (ref "IC3") (pin "8") (pinfunction "PCM_SYNC_8") (pintype "bidirectional"))
    )
    (net (code "91") (name "unconnected-(IC3-SPI_CLOCK-Pad6)") (class "Default")
      (node (ref "IC3") (pin "6") (pinfunction "SPI_CLOCK_6") (pintype "bidirectional"))
    )
    (net (code "92") (name "unconnected-(IC3-SPI_CSB-Pad23)") (class "Default")
      (node (ref "IC3") (pin "23") (pinfunction "SPI_CSB_23") (pintype "bidirectional"))
    )
    (net (code "93") (name "unconnected-(IC3-SPI_MISO-Pad24)") (class "Default")
      (node (ref "IC3") (pin "24") (pinfunction "SPI_MISO_24") (pintype "bidirectional"))
    )
    (net (code "94") (name "unconnected-(IC3-SPI_MOSI-Pad2)") (class "Default")
      (node (ref "IC3") (pin "2") (pinfunction "SPI_MOSI_2") (pintype "bidirectional"))
    )
    (net (code "95") (name "unconnected-(IC3-USB_D+-Pad17)") (class "Default")
      (node (ref "IC3") (pin "17") (pinfunction "USB_D+_17") (pintype "bidirectional"))
    )
    (net (code "96") (name "unconnected-(IC3-USB_D--Pad18)") (class "Default")
      (node (ref "IC3") (pin "18") (pinfunction "USB_D-_18") (pintype "bidirectional"))
    )
    (net (code "97") (name "unconnected-(IC10-PGOOD-Pad1)") (class "Default")
      (node (ref "IC10") (pin "1") (pinfunction "PGOOD_1") (pintype "open_collector"))
    )
  )
)
